# SHT31.net
KiCad netlist of a schematic drawn in EAGLE
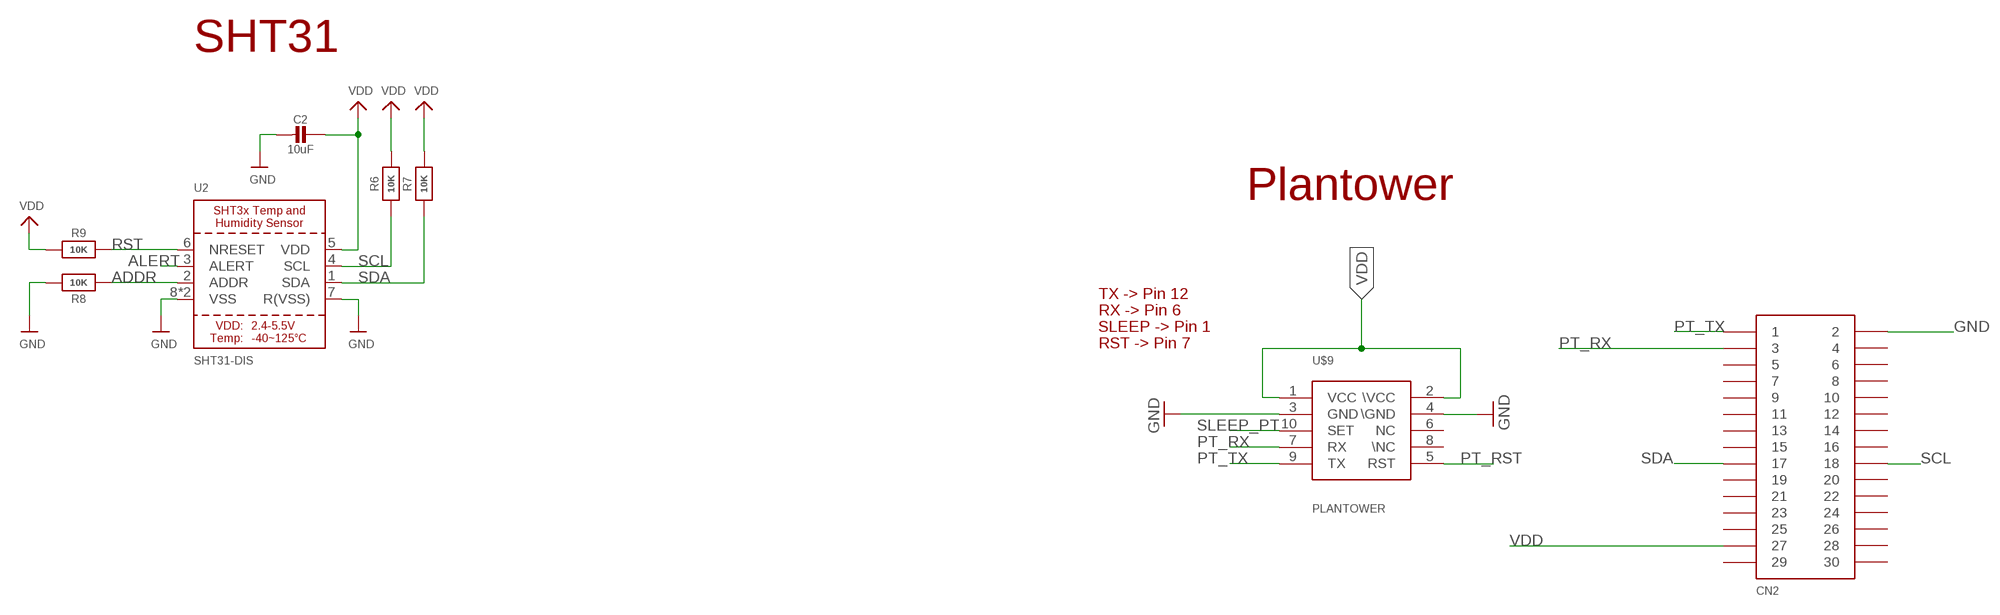
[diagram p0: schematic, sheet 1]

(export (version "E")
  (design (tool "Eeschema 10.0.6"))
  (components
    (comp (ref "C2")
      (value "10uF")
      (footprint "eagle-import:_1206")
      (libsource (lib "eagle-import") (part "CAP_CERAMIC_1206"))
    )
    (comp (ref "CN2")
      (value "CON_PINHD-2X15")
      (footprint "eagle-import:2X15SMD")
      (libsource (lib "eagle-import") (part "CON_PINHD-2X15"))
    )
    (comp (ref "R6")
      (value "10K")
      (footprint "eagle-import:_1206MP")
      (libsource (lib "eagle-import") (part "RESISTOR_1206MP"))
    )
    (comp (ref "R7")
      (value "10K")
      (footprint "eagle-import:_1206MP")
      (libsource (lib "eagle-import") (part "RESISTOR_1206MP"))
    )
    (comp (ref "R8")
      (value "10K")
      (footprint "eagle-import:_1206MP")
      (libsource (lib "eagle-import") (part "RESISTOR_1206MP"))
    )
    (comp (ref "R9")
      (value "10K")
      (footprint "eagle-import:_1206MP")
      (libsource (lib "eagle-import") (part "RESISTOR_1206MP"))
    )
    (comp (ref "U$9")
      (value "PLANTOWER")
      (footprint "eagle-import:CONN")
      (libsource (lib "eagle-import") (part "PLANTOWER"))
    )
    (comp (ref "U2")
      (value "SHT31-DIS")
      (footprint "eagle-import:SHT3X")
      (libsource (lib "eagle-import") (part "SHT3X"))
    )
  )
  (nets
    (net (code "1") (name "/ADDR") (class "Default")
      (node (ref "R8") (pin "1") (pinfunction "1_1") (pintype "passive"))
      (node (ref "U2") (pin "2") (pinfunction "ADDR_2") (pintype "bidirectional"))
    )
    (net (code "2") (name "/ALERT") (class "Default")
      (node (ref "U2") (pin "3") (pinfunction "ALERT_3") (pintype "bidirectional"))
    )
    (net (code "3") (name "/PT_RST") (class "Default")
      (node (ref "U$9") (pin "5") (pinfunction "RST_5") (pintype "bidirectional"))
    )
    (net (code "4") (name "/PT_RX") (class "Default")
      (node (ref "CN2") (pin "P$3") (pinfunction "3_P$3") (pintype "bidirectional"))
      (node (ref "U$9") (pin "7") (pinfunction "RX_7") (pintype "bidirectional"))
    )
    (net (code "5") (name "/PT_TX") (class "Default")
      (node (ref "CN2") (pin "P$1") (pinfunction "1_P$1") (pintype "bidirectional"))
      (node (ref "U$9") (pin "9") (pinfunction "TX_9") (pintype "bidirectional"))
    )
    (net (code "6") (name "/RST") (class "Default")
      (node (ref "R9") (pin "2") (pinfunction "2_2") (pintype "passive"))
      (node (ref "U2") (pin "6") (pinfunction "NRESET_6") (pintype "bidirectional"))
    )
    (net (code "7") (name "/SCL") (class "Default")
      (node (ref "CN2") (pin "P$18") (pinfunction "18_P$18") (pintype "bidirectional"))
      (node (ref "R6") (pin "1") (pinfunction "1_1") (pintype "passive"))
      (node (ref "U2") (pin "4") (pinfunction "SCL_4") (pintype "bidirectional"))
    )
    (net (code "8") (name "/SDA") (class "Default")
      (node (ref "CN2") (pin "P$17") (pinfunction "17_P$17") (pintype "bidirectional"))
      (node (ref "R7") (pin "1") (pinfunction "1_1") (pintype "passive"))
      (node (ref "U2") (pin "1") (pinfunction "SDA_1") (pintype "bidirectional"))
    )
    (net (code "9") (name "/SLEEP_PT") (class "Default")
      (node (ref "U$9") (pin "10") (pinfunction "SET_10") (pintype "bidirectional"))
    )
    (net (code "10") (name "GND") (class "Default")
      (node (ref "C2") (pin "2") (pinfunction "2_2") (pintype "passive"))
      (node (ref "CN2") (pin "P$2") (pinfunction "2_P$2") (pintype "bidirectional"))
      (node (ref "R8") (pin "2") (pinfunction "2_2") (pintype "passive"))
      (node (ref "U$9") (pin "3") (pinfunction "GND_3") (pintype "bidirectional"))
      (node (ref "U$9") (pin "4") (pinfunction "\\GND_4") (pintype "bidirectional"))
      (node (ref "U2") (pin "7") (pinfunction "R(VSS)_7") (pintype "bidirectional"))
      (node (ref "U2") (pin "8") (pinfunction "VSS_8") (pintype "power_in"))
      (node (ref "U2") (pin "THERMAL") (pinfunction "VSS_THERMAL") (pintype "power_in"))
    )
    (net (code "11") (name "VDD") (class "Default")
      (node (ref "C2") (pin "1") (pinfunction "1_1") (pintype "passive"))
      (node (ref "CN2") (pin "P$27") (pinfunction "27_P$27") (pintype "bidirectional"))
      (node (ref "R6") (pin "2") (pinfunction "2_2") (pintype "passive"))
      (node (ref "R7") (pin "2") (pinfunction "2_2") (pintype "passive"))
      (node (ref "R9") (pin "1") (pinfunction "1_1") (pintype "passive"))
      (node (ref "U$9") (pin "1") (pinfunction "VCC_1") (pintype "bidirectional"))
      (node (ref "U$9") (pin "2") (pinfunction "\\VCC_2") (pintype "bidirectional"))
      (node (ref "U2") (pin "5") (pinfunction "VDD_5") (pintype "power_in"))
    )
    (net (code "12") (name "unconnected-(CN2-4-PadP$4)") (class "Default")
      (node (ref "CN2") (pin "P$4") (pinfunction "4_P$4") (pintype "bidirectional"))
    )
    (net (code "13") (name "unconnected-(CN2-5-PadP$5)") (class "Default")
      (node (ref "CN2") (pin "P$5") (pinfunction "5_P$5") (pintype "bidirectional"))
    )
    (net (code "14") (name "unconnected-(CN2-6-PadP$6)") (class "Default")
      (node (ref "CN2") (pin "P$6") (pinfunction "6_P$6") (pintype "bidirectional"))
    )
    (net (code "15") (name "unconnected-(CN2-7-PadP$7)") (class "Default")
      (node (ref "CN2") (pin "P$7") (pinfunction "7_P$7") (pintype "bidirectional"))
    )
    (net (code "16") (name "unconnected-(CN2-8-PadP$8)") (class "Default")
      (node (ref "CN2") (pin "P$8") (pinfunction "8_P$8") (pintype "bidirectional"))
    )
    (net (code "17") (name "unconnected-(CN2-9-PadP$9)") (class "Default")
      (node (ref "CN2") (pin "P$9") (pinfunction "9_P$9") (pintype "bidirectional"))
    )
    (net (code "18") (name "unconnected-(CN2-10-PadP$10)") (class "Default")
      (node (ref "CN2") (pin "P$10") (pinfunction "10_P$10") (pintype "bidirectional"))
    )
    (net (code "19") (name "unconnected-(CN2-11-PadP$11)") (class "Default")
      (node (ref "CN2") (pin "P$11") (pinfunction "11_P$11") (pintype "bidirectional"))
    )
    (net (code "20") (name "unconnected-(CN2-12-PadP$12)") (class "Default")
      (node (ref "CN2") (pin "P$12") (pinfunction "12_P$12") (pintype "bidirectional"))
    )
    (net (code "21") (name "unconnected-(CN2-13-PadP$13)") (class "Default")
      (node (ref "CN2") (pin "P$13") (pinfunction "13_P$13") (pintype "bidirectional"))
    )
    (net (code "22") (name "unconnected-(CN2-14-PadP$14)") (class "Default")
      (node (ref "CN2") (pin "P$14") (pinfunction "14_P$14") (pintype "bidirectional"))
    )
    (net (code "23") (name "unconnected-(CN2-15-PadP$15)") (class "Default")
      (node (ref "CN2") (pin "P$15") (pinfunction "15_P$15") (pintype "bidirectional"))
    )
    (net (code "24") (name "unconnected-(CN2-16-PadP$16)") (class "Default")
      (node (ref "CN2") (pin "P$16") (pinfunction "16_P$16") (pintype "bidirectional"))
    )
    (net (code "25") (name "unconnected-(CN2-19-PadP$19)") (class "Default")
      (node (ref "CN2") (pin "P$19") (pinfunction "19_P$19") (pintype "bidirectional"))
    )
    (net (code "26") (name "unconnected-(CN2-20-PadP$20)") (class "Default")
      (node (ref "CN2") (pin "P$20") (pinfunction "20_P$20") (pintype "bidirectional"))
    )
    (net (code "27") (name "unconnected-(CN2-21-PadP$21)") (class "Default")
      (node (ref "CN2") (pin "P$21") (pinfunction "21_P$21") (pintype "bidirectional"))
    )
    (net (code "28") (name "unconnected-(CN2-22-PadP$22)") (class "Default")
      (node (ref "CN2") (pin "P$22") (pinfunction "22_P$22") (pintype "bidirectional"))
    )
    (net (code "29") (name "unconnected-(CN2-23-PadP$23)") (class "Default")
      (node (ref "CN2") (pin "P$23") (pinfunction "23_P$23") (pintype "bidirectional"))
    )
    (net (code "30") (name "unconnected-(CN2-24-PadP$24)") (class "Default")
      (node (ref "CN2") (pin "P$24") (pinfunction "24_P$24") (pintype "bidirectional"))
    )
    (net (code "31") (name "unconnected-(CN2-25-PadP$25)") (class "Default")
      (node (ref "CN2") (pin "P$25") (pinfunction "25_P$25") (pintype "bidirectional"))
    )
    (net (code "32") (name "unconnected-(CN2-26-PadP$26)") (class "Default")
      (node (ref "CN2") (pin "P$26") (pinfunction "26_P$26") (pintype "bidirectional"))
    )
    (net (code "33") (name "unconnected-(CN2-28-PadP$28)") (class "Default")
      (node (ref "CN2") (pin "P$28") (pinfunction "28_P$28") (pintype "bidirectional"))
    )
    (net (code "34") (name "unconnected-(CN2-29-PadP$29)") (class "Default")
      (node (ref "CN2") (pin "P$29") (pinfunction "29_P$29") (pintype "bidirectional"))
    )
    (net (code "35") (name "unconnected-(CN2-30-PadP$30)") (class "Default")
      (node (ref "CN2") (pin "P$30") (pinfunction "30_P$30") (pintype "bidirectional"))
    )
    (net (code "36") (name "unconnected-(U$9-NC-Pad6)") (class "Default")
      (node (ref "U$9") (pin "6") (pinfunction "NC_6") (pintype "bidirectional"))
    )
    (net (code "37") (name "unconnected-(U$9-\\NC-Pad8)") (class "Default")
      (node (ref "U$9") (pin "8") (pinfunction "\\NC_8") (pintype "bidirectional"))
    )
  )
)
